# poesp_1_1.net
KiCad netlist of a schematic drawn in EAGLE
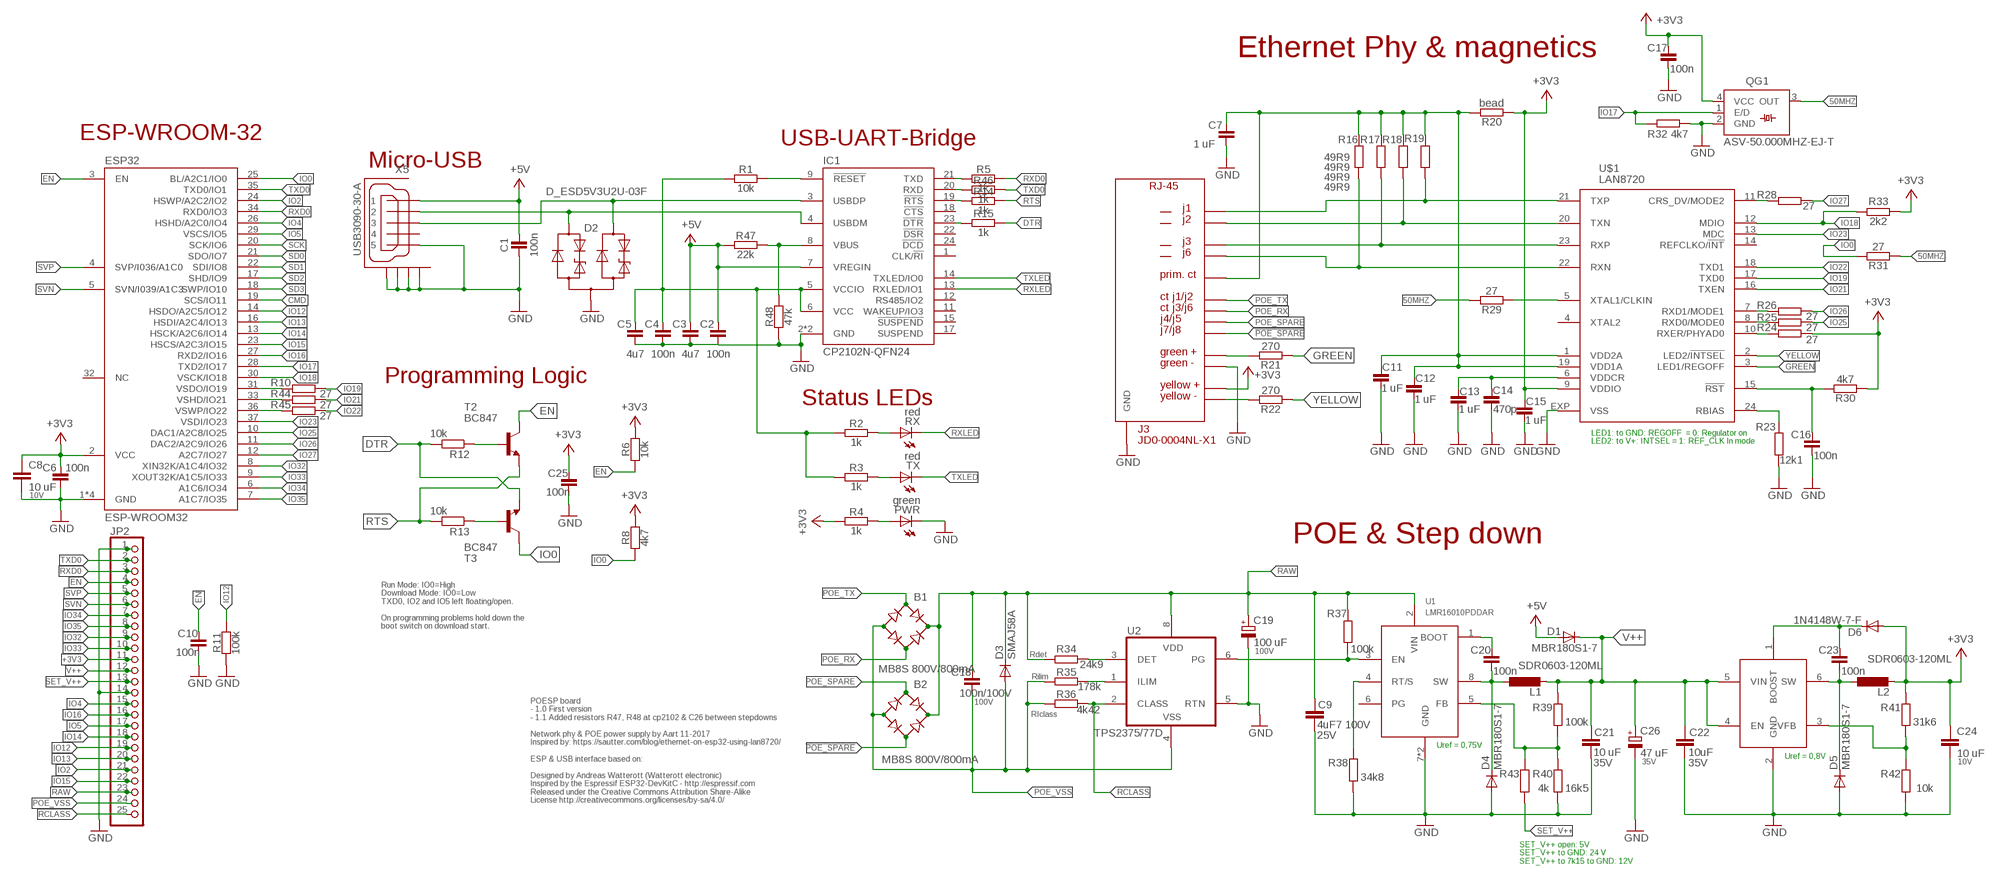
[diagram p0: schematic, sheet 1]

(export (version "E")
  (design (tool "Eeschema 10.0.6"))
  (components
    (comp (ref "B1")
      (value "MB8S 800V/800mA")
      (footprint "eagle-import:MBS")
      (libsource (lib "eagle-import") (part "BS10"))
    )
    (comp (ref "B2")
      (value "MB8S 800V/800mA")
      (footprint "eagle-import:MBS")
      (libsource (lib "eagle-import") (part "BS10"))
    )
    (comp (ref "C1")
      (value "100n")
      (footprint "eagle-import:C0603")
      (libsource (lib "eagle-import") (part "CAPACITOR-0603"))
    )
    (comp (ref "C2")
      (value "100n")
      (footprint "eagle-import:C0603")
      (libsource (lib "eagle-import") (part "CAPACITOR-0603"))
    )
    (comp (ref "C3")
      (value "4u7")
      (footprint "eagle-import:C0805")
      (libsource (lib "eagle-import") (part "CAPACITOR-0805"))
    )
    (comp (ref "C4")
      (value "100n")
      (footprint "eagle-import:C0603")
      (libsource (lib "eagle-import") (part "CAPACITOR-0603"))
    )
    (comp (ref "C5")
      (value "4u7")
      (footprint "eagle-import:C0805")
      (libsource (lib "eagle-import") (part "CAPACITOR-0805"))
    )
    (comp (ref "C6")
      (value "100n")
      (footprint "eagle-import:C0603")
      (libsource (lib "eagle-import") (part "CAPACITOR-0603"))
    )
    (comp (ref "C7")
      (value "1 uF")
      (footprint "eagle-import:C0603")
      (libsource (lib "eagle-import") (part "CAPACITOR-0603"))
    )
    (comp (ref "C8")
      (value "10 uF")
      (footprint "eagle-import:C0805K")
      (fields (field (name "VOLTAGE") "10V"))
      (libsource (lib "eagle-import") (part "C-EUC0805K"))
    )
    (comp (ref "C9")
      (value "4uF7 100V")
      (footprint "eagle-import:C1210K")
      (fields (field (name "VOLTAGE") "25V"))
      (libsource (lib "eagle-import") (part "C-EUC1210K"))
    )
    (comp (ref "C10")
      (value "100n")
      (footprint "eagle-import:C0603")
      (libsource (lib "eagle-import") (part "CAPACITOR-0603"))
    )
    (comp (ref "C11")
      (value "1 uF")
      (footprint "eagle-import:C0603")
      (libsource (lib "eagle-import") (part "CAPACITOR-0603"))
    )
    (comp (ref "C12")
      (value "1 uF")
      (footprint "eagle-import:C0603")
      (libsource (lib "eagle-import") (part "CAPACITOR-0603"))
    )
    (comp (ref "C13")
      (value "1 uF")
      (footprint "eagle-import:C0603")
      (libsource (lib "eagle-import") (part "CAPACITOR-0603"))
    )
    (comp (ref "C14")
      (value "470p")
      (footprint "eagle-import:C0603")
      (libsource (lib "eagle-import") (part "CAPACITOR-0603"))
    )
    (comp (ref "C15")
      (value "1 uF")
      (footprint "eagle-import:C0603")
      (libsource (lib "eagle-import") (part "CAPACITOR-0603"))
    )
    (comp (ref "C16")
      (value "100n")
      (footprint "eagle-import:C0603")
      (libsource (lib "eagle-import") (part "CAPACITOR-0603"))
    )
    (comp (ref "C17")
      (value "100n")
      (footprint "eagle-import:C0603")
      (libsource (lib "eagle-import") (part "CAPACITOR-0603"))
    )
    (comp (ref "C18")
      (value "100n/100V")
      (footprint "eagle-import:C0603")
      (fields (field (name "VOLTAGE") "100V"))
      (libsource (lib "eagle-import") (part "CAPACITOR-0603"))
    )
    (comp (ref "C19")
      (value "100 uF")
      (footprint "eagle-import:E5-10,5")
      (fields (field (name "VOLTAGE") "100V"))
      (libsource (lib "eagle-import") (part "CPOL-EUE5-10.5"))
    )
    (comp (ref "C20")
      (value "100n")
      (footprint "eagle-import:C0603")
      (libsource (lib "eagle-import") (part "CAPACITOR-0603"))
    )
    (comp (ref "C21")
      (value "10 uF")
      (footprint "eagle-import:C1210K")
      (fields (field (name "VOLTAGE") "35V"))
      (libsource (lib "eagle-import") (part "C-EUC1210K"))
    )
    (comp (ref "C22")
      (value "10uF")
      (footprint "eagle-import:C1210K")
      (fields (field (name "VOLTAGE") "35V"))
      (libsource (lib "eagle-import") (part "C-EUC1210K"))
    )
    (comp (ref "C23")
      (value "100n")
      (footprint "eagle-import:C0603")
      (libsource (lib "eagle-import") (part "CAPACITOR-0603"))
    )
    (comp (ref "C24")
      (value "10 uF")
      (footprint "eagle-import:C0805K")
      (fields (field (name "VOLTAGE") "10V"))
      (libsource (lib "eagle-import") (part "C-EUC0805K"))
    )
    (comp (ref "C25")
      (value "100n")
      (footprint "eagle-import:C0603")
      (libsource (lib "eagle-import") (part "CAPACITOR-0603"))
    )
    (comp (ref "C26")
      (value "47 uF")
      (footprint "eagle-import:E2,5-6E")
      (fields (field (name "VOLTAGE") "35V"))
      (libsource (lib "eagle-import") (part "CPOL-EUE2,5-6E"))
    )
    (comp (ref "D1")
      (value "MBR180S1-7")
      (footprint "eagle-import:SOD-123_MINI-SMA")
      (libsource (lib "eagle-import") (part "CGRM400-G1"))
    )
    (comp (ref "D2")
      (value "D_ESD5V3U2U-03F")
      (footprint "eagle-import:SOT723")
      (libsource (lib "eagle-import") (part "D_ESD5V3U2U-03F"))
    )
    (comp (ref "D3")
      (value "SMAJ58A")
      (footprint "eagle-import:DO214AC")
      (libsource (lib "eagle-import") (part "DIODE-DO214AC"))
    )
    (comp (ref "D4")
      (value "MBR180S1-7")
      (footprint "eagle-import:SOD-123_MINI-SMA")
      (libsource (lib "eagle-import") (part "CGRM400-G1"))
    )
    (comp (ref "D5")
      (value "MBR180S1-7")
      (footprint "eagle-import:SOD-123_MINI-SMA")
      (libsource (lib "eagle-import") (part "CGRM400-G1"))
    )
    (comp (ref "D6")
      (value "1N4148W-7-F")
      (footprint "eagle-import:SOD-123_MINI-SMA")
      (libsource (lib "eagle-import") (part "CGRM400-G1"))
    )
    (comp (ref "ESP32")
      (value "ESP-WROOM32")
      (footprint "eagle-import:ESP-WROOM32")
      (libsource (lib "eagle-import") (part "ESP-WROOM32"))
    )
    (comp (ref "IC1")
      (value "CP2102N-QFN24")
      (footprint "eagle-import:QFN24-PAD")
      (libsource (lib "eagle-import") (part "CP2102N-QFN24"))
    )
    (comp (ref "IC3")
      (value "MCP16301/H")
      (footprint "eagle-import:SOT23-6")
      (libsource (lib "eagle-import") (part "MCP16301/H"))
    )
    (comp (ref "J3")
      (value "JD0-0004NL-X1")
      (footprint "eagle-import:JD0")
      (libsource (lib "eagle-import") (part "JD0-0004NL-X1"))
    )
    (comp (ref "JP2")
      (value "PINHD-1X25")
      (footprint "eagle-import:1X25")
      (libsource (lib "eagle-import") (part "PINHD-1X25"))
    )
    (comp (ref "L1")
      (value "SDR0603-120ML")
      (footprint "eagle-import:POWER-CHOKE_WE-TPC")
      (libsource (lib "eagle-import") (part "L-EUWE-TPC"))
    )
    (comp (ref "L2")
      (value "SDR0603-120ML")
      (footprint "eagle-import:POWER-CHOKE_WE-TPC")
      (libsource (lib "eagle-import") (part "L-EUWE-TPC"))
    )
    (comp (ref "PWR")
      (value "green")
      (footprint "eagle-import:C0603")
      (libsource (lib "eagle-import") (part "LED-0603"))
    )
    (comp (ref "QG1")
      (value "ASV-50.000MHZ-EJ-T")
      (footprint "eagle-import:SM77H")
      (libsource (lib "eagle-import") (part "SM77H"))
    )
    (comp (ref "R1")
      (value "10k")
      (footprint "eagle-import:C0603")
      (libsource (lib "eagle-import") (part "RESISTOR-0603"))
    )
    (comp (ref "R2")
      (value "1k")
      (footprint "eagle-import:C0603")
      (libsource (lib "eagle-import") (part "RESISTOR-0603"))
    )
    (comp (ref "R3")
      (value "1k")
      (footprint "eagle-import:C0603")
      (libsource (lib "eagle-import") (part "RESISTOR-0603"))
    )
    (comp (ref "R4")
      (value "1k")
      (footprint "eagle-import:C0603")
      (libsource (lib "eagle-import") (part "RESISTOR-0603"))
    )
    (comp (ref "R5")
      (value "1k")
      (footprint "eagle-import:C0603")
      (libsource (lib "eagle-import") (part "RESISTOR-0603"))
    )
    (comp (ref "R6")
      (value "10k")
      (footprint "eagle-import:C0603")
      (libsource (lib "eagle-import") (part "RESISTOR-0603"))
    )
    (comp (ref "R8")
      (value "4k7")
      (footprint "eagle-import:C0603")
      (libsource (lib "eagle-import") (part "RESISTOR-0603"))
    )
    (comp (ref "R10")
      (value "27")
      (footprint "eagle-import:C0603")
      (libsource (lib "eagle-import") (part "RESISTOR-0603"))
    )
    (comp (ref "R11")
      (value "100k")
      (footprint "eagle-import:C0603")
      (libsource (lib "eagle-import") (part "RESISTOR-0603"))
    )
    (comp (ref "R12")
      (value "10k")
      (footprint "eagle-import:R0603")
      (libsource (lib "eagle-import") (part "R-EU_R0603"))
    )
    (comp (ref "R13")
      (value "10k")
      (footprint "eagle-import:R0603")
      (libsource (lib "eagle-import") (part "R-EU_R0603"))
    )
    (comp (ref "R14")
      (value "1k")
      (footprint "eagle-import:C0603")
      (libsource (lib "eagle-import") (part "RESISTOR-0603"))
    )
    (comp (ref "R15")
      (value "1k")
      (footprint "eagle-import:C0603")
      (libsource (lib "eagle-import") (part "RESISTOR-0603"))
    )
    (comp (ref "R16")
      (value "49R9")
      (footprint "eagle-import:C0603")
      (libsource (lib "eagle-import") (part "RESISTOR-0603"))
    )
    (comp (ref "R17")
      (value "49R9")
      (footprint "eagle-import:C0603")
      (libsource (lib "eagle-import") (part "RESISTOR-0603"))
    )
    (comp (ref "R18")
      (value "49R9")
      (footprint "eagle-import:C0603")
      (libsource (lib "eagle-import") (part "RESISTOR-0603"))
    )
    (comp (ref "R19")
      (value "49R9")
      (footprint "eagle-import:C0603")
      (libsource (lib "eagle-import") (part "RESISTOR-0603"))
    )
    (comp (ref "R20")
      (value "bead")
      (footprint "eagle-import:C0603")
      (libsource (lib "eagle-import") (part "RESISTOR-0603"))
    )
    (comp (ref "R21")
      (value "270")
      (footprint "eagle-import:C0603")
      (libsource (lib "eagle-import") (part "RESISTOR-0603"))
    )
    (comp (ref "R22")
      (value "270")
      (footprint "eagle-import:C0603")
      (libsource (lib "eagle-import") (part "RESISTOR-0603"))
    )
    (comp (ref "R23")
      (value "12k1")
      (footprint "eagle-import:C0603")
      (libsource (lib "eagle-import") (part "RESISTOR-0603"))
    )
    (comp (ref "R24")
      (value "27")
      (footprint "eagle-import:C0603")
      (libsource (lib "eagle-import") (part "RESISTOR-0603"))
    )
    (comp (ref "R25")
      (value "27")
      (footprint "eagle-import:C0603")
      (libsource (lib "eagle-import") (part "RESISTOR-0603"))
    )
    (comp (ref "R26")
      (value "27")
      (footprint "eagle-import:C0603")
      (libsource (lib "eagle-import") (part "RESISTOR-0603"))
    )
    (comp (ref "R28")
      (value "27")
      (footprint "eagle-import:C0603")
      (libsource (lib "eagle-import") (part "RESISTOR-0603"))
    )
    (comp (ref "R29")
      (value "27")
      (footprint "eagle-import:C0603")
      (libsource (lib "eagle-import") (part "RESISTOR-0603"))
    )
    (comp (ref "R30")
      (value "4k7")
      (footprint "eagle-import:C0603")
      (libsource (lib "eagle-import") (part "RESISTOR-0603"))
    )
    (comp (ref "R31")
      (value "27")
      (footprint "eagle-import:C0603")
      (libsource (lib "eagle-import") (part "RESISTOR-0603"))
    )
    (comp (ref "R32")
      (value "4k7")
      (footprint "eagle-import:C0603")
      (libsource (lib "eagle-import") (part "RESISTOR-0603"))
    )
    (comp (ref "R33")
      (value "2k2")
      (footprint "eagle-import:C0603")
      (libsource (lib "eagle-import") (part "RESISTOR-0603"))
    )
    (comp (ref "R34")
      (value "24k9")
      (footprint "eagle-import:C0603")
      (fields (field (name "FUNCTION") "Rdet"))
      (libsource (lib "eagle-import") (part "RESISTOR-0603"))
    )
    (comp (ref "R35")
      (value "178k")
      (footprint "eagle-import:C0603")
      (fields (field (name "FUNCTION") "Rilim"))
      (libsource (lib "eagle-import") (part "RESISTOR-0603"))
    )
    (comp (ref "R36")
      (value "4k42")
      (footprint "eagle-import:C0603")
      (fields (field (name "FUNCTION") "RIclass"))
      (libsource (lib "eagle-import") (part "RESISTOR-0603"))
    )
    (comp (ref "R37")
      (value "100k")
      (footprint "eagle-import:C0603")
      (libsource (lib "eagle-import") (part "RESISTOR-0603"))
    )
    (comp (ref "R38")
      (value "34k8")
      (footprint "eagle-import:C0603")
      (fields (field (name "FUNCTION") "Rdet"))
      (libsource (lib "eagle-import") (part "RESISTOR-0603"))
    )
    (comp (ref "R39")
      (value "100k")
      (footprint "eagle-import:C0603")
      (fields (field (name "FUNCTION") "Rdet"))
      (libsource (lib "eagle-import") (part "RESISTOR-0603"))
    )
    (comp (ref "R40")
      (value "16k5")
      (footprint "eagle-import:C0603")
      (fields (field (name "FUNCTION") "Rdet"))
      (libsource (lib "eagle-import") (part "RESISTOR-0603"))
    )
    (comp (ref "R41")
      (value "31k6")
      (footprint "eagle-import:C0603")
      (fields (field (name "FUNCTION") "Rdet"))
      (libsource (lib "eagle-import") (part "RESISTOR-0603"))
    )
    (comp (ref "R42")
      (value "10k")
      (footprint "eagle-import:C0603")
      (fields (field (name "FUNCTION") "Rdet"))
      (libsource (lib "eagle-import") (part "RESISTOR-0603"))
    )
    (comp (ref "R43")
      (value "4k")
      (footprint "eagle-import:C0603")
      (fields (field (name "FUNCTION") "Rdet"))
      (libsource (lib "eagle-import") (part "RESISTOR-0603"))
    )
    (comp (ref "R44")
      (value "27")
      (footprint "eagle-import:C0603")
      (libsource (lib "eagle-import") (part "RESISTOR-0603"))
    )
    (comp (ref "R45")
      (value "27")
      (footprint "eagle-import:C0603")
      (libsource (lib "eagle-import") (part "RESISTOR-0603"))
    )
    (comp (ref "R46")
      (value "1k")
      (footprint "eagle-import:C0603")
      (libsource (lib "eagle-import") (part "RESISTOR-0603"))
    )
    (comp (ref "R47")
      (value "22k")
      (footprint "eagle-import:C0603")
      (libsource (lib "eagle-import") (part "RESISTOR-0603"))
    )
    (comp (ref "R48")
      (value "47k")
      (footprint "eagle-import:C0603")
      (libsource (lib "eagle-import") (part "RESISTOR-0603"))
    )
    (comp (ref "RX")
      (value "red")
      (footprint "eagle-import:C0603")
      (libsource (lib "eagle-import") (part "LED-0603"))
    )
    (comp (ref "T2")
      (value "BC847")
      (footprint "eagle-import:SOT23")
      (libsource (lib "eagle-import") (part "BC847"))
    )
    (comp (ref "T3")
      (value "BC847")
      (footprint "eagle-import:SOT23")
      (libsource (lib "eagle-import") (part "BC847"))
    )
    (comp (ref "TX")
      (value "red")
      (footprint "eagle-import:C0603")
      (libsource (lib "eagle-import") (part "LED-0603"))
    )
    (comp (ref "U$1")
      (value "LAN8720")
      (footprint "eagle-import:QFN24")
      (libsource (lib "eagle-import") (part "LAN8720"))
    )
    (comp (ref "U1")
      (value "LMR16010PDDAR")
      (footprint "eagle-import:HSOIC8")
      (libsource (lib "eagle-import") (part "LMR16010PDDAR"))
    )
    (comp (ref "U2")
      (value "TPS2375/77D")
      (footprint "eagle-import:SO08")
      (libsource (lib "eagle-import") (part "TPS2375/77D"))
    )
    (comp (ref "X5")
      (value "USB3090-30-A")
      (footprint "eagle-import:USB3090-30-A")
      (libsource (lib "eagle-import") (part "USB3090-30-A"))
    )
  )
  (nets
    (net (code "1") (name "+3V3") (class "Default")
      (node (ref "C15") (pin "2") (pinfunction "2_2") (pintype "passive"))
      (node (ref "C17") (pin "2") (pinfunction "2_2") (pintype "passive"))
      (node (ref "C24") (pin "1") (pinfunction "1_1") (pintype "passive"))
      (node (ref "C25") (pin "2") (pinfunction "2_2") (pintype "passive"))
      (node (ref "C6") (pin "2") (pinfunction "2_2") (pintype "passive"))
      (node (ref "C8") (pin "1") (pinfunction "1_1") (pintype "passive"))
      (node (ref "D6") (pin "A") (pinfunction "A_A") (pintype "passive"))
      (node (ref "ESP32") (pin "2") (pinfunction "VCC_2") (pintype "power_in"))
      (node (ref "J3") (pin "P$14") (pinfunction "P$14_P$14") (pintype "bidirectional"))
      (node (ref "JP2") (pin "11") (pinfunction "11_11") (pintype "passive"))
      (node (ref "L2") (pin "2") (pinfunction "2_2") (pintype "passive"))
      (node (ref "QG1") (pin "4") (pinfunction "VCC_4") (pintype "power_in"))
      (node (ref "R20") (pin "1") (pinfunction "1_1") (pintype "passive"))
      (node (ref "R24") (pin "1") (pinfunction "1_1") (pintype "passive"))
      (node (ref "R30") (pin "1") (pinfunction "1_1") (pintype "passive"))
      (node (ref "R33") (pin "1") (pinfunction "1_1") (pintype "passive"))
      (node (ref "R4") (pin "1") (pinfunction "1_1") (pintype "passive"))
      (node (ref "R41") (pin "1") (pinfunction "1_1") (pintype "passive"))
      (node (ref "R6") (pin "2") (pinfunction "2_2") (pintype "passive"))
      (node (ref "R8") (pin "2") (pinfunction "2_2") (pintype "passive"))
      (node (ref "U$1") (pin "9") (pinfunction "VDDIO_9") (pintype "power_in"))
    )
    (net (code "2") (name "+5V") (class "Default")
      (node (ref "C1") (pin "2") (pinfunction "2_2") (pintype "passive"))
      (node (ref "C2") (pin "2") (pinfunction "2_2") (pintype "passive"))
      (node (ref "C3") (pin "2") (pinfunction "2_2") (pintype "passive"))
      (node (ref "D1") (pin "A") (pinfunction "A_A") (pintype "passive"))
      (node (ref "IC1") (pin "7") (pinfunction "VREGIN_7") (pintype "power_in"))
      (node (ref "R47") (pin "1") (pinfunction "1_1") (pintype "passive"))
      (node (ref "X5") (pin "1") (pinfunction "1_1") (pintype "input"))
    )
    (net (code "3") (name "/~{POE_SPARE}") (class "Default")
      (node (ref "B2") (pin "AC2") (pinfunction "AC2_AC2") (pintype "passive"))
      (node (ref "J3") (pin "P$8") (pinfunction "P$8_P$8") (pintype "bidirectional"))
    )
    (net (code "4") (name "50MHZ") (class "Default")
      (node (ref "QG1") (pin "3") (pinfunction "OUT_3") (pintype "output"))
      (node (ref "R29") (pin "2") (pinfunction "2_2") (pintype "passive"))
      (node (ref "R31") (pin "1") (pinfunction "1_1") (pintype "passive"))
    )
    (net (code "5") (name "CMD") (class "Default")
      (node (ref "ESP32") (pin "19") (pinfunction "SCS/IO11_19") (pintype "bidirectional"))
    )
    (net (code "6") (name "DTR") (class "Default")
      (node (ref "R12") (pin "2") (pinfunction "2_2") (pintype "passive"))
      (node (ref "R15") (pin "2") (pinfunction "2_2") (pintype "passive"))
      (node (ref "T3") (pin "2") (pinfunction "E_2") (pintype "passive"))
    )
    (net (code "7") (name "EN") (class "Default")
      (node (ref "C10") (pin "2") (pinfunction "2_2") (pintype "passive"))
      (node (ref "ESP32") (pin "3") (pinfunction "EN_3") (pintype "bidirectional"))
      (node (ref "JP2") (pin "4") (pinfunction "4_4") (pintype "passive"))
      (node (ref "R6") (pin "1") (pinfunction "1_1") (pintype "passive"))
      (node (ref "T2") (pin "3") (pinfunction "C_3") (pintype "passive"))
    )
    (net (code "8") (name "GND") (class "Default")
      (node (ref "C1") (pin "1") (pinfunction "1_1") (pintype "passive"))
      (node (ref "C10") (pin "1") (pinfunction "1_1") (pintype "passive"))
      (node (ref "C11") (pin "1") (pinfunction "1_1") (pintype "passive"))
      (node (ref "C12") (pin "1") (pinfunction "1_1") (pintype "passive"))
      (node (ref "C13") (pin "1") (pinfunction "1_1") (pintype "passive"))
      (node (ref "C14") (pin "1") (pinfunction "1_1") (pintype "passive"))
      (node (ref "C15") (pin "1") (pinfunction "1_1") (pintype "passive"))
      (node (ref "C16") (pin "1") (pinfunction "1_1") (pintype "passive"))
      (node (ref "C17") (pin "1") (pinfunction "1_1") (pintype "passive"))
      (node (ref "C19") (pin "-") (pinfunction "-_-") (pintype "passive"))
      (node (ref "C2") (pin "1") (pinfunction "1_1") (pintype "passive"))
      (node (ref "C21") (pin "2") (pinfunction "2_2") (pintype "passive"))
      (node (ref "C22") (pin "2") (pinfunction "2_2") (pintype "passive"))
      (node (ref "C24") (pin "2") (pinfunction "2_2") (pintype "passive"))
      (node (ref "C25") (pin "1") (pinfunction "1_1") (pintype "passive"))
      (node (ref "C26") (pin "-") (pinfunction "-_-") (pintype "passive"))
      (node (ref "C3") (pin "1") (pinfunction "1_1") (pintype "passive"))
      (node (ref "C4") (pin "1") (pinfunction "1_1") (pintype "passive"))
      (node (ref "C5") (pin "1") (pinfunction "1_1") (pintype "passive"))
      (node (ref "C6") (pin "1") (pinfunction "1_1") (pintype "passive"))
      (node (ref "C7") (pin "1") (pinfunction "1_1") (pintype "passive"))
      (node (ref "C8") (pin "2") (pinfunction "2_2") (pintype "passive"))
      (node (ref "C9") (pin "2") (pinfunction "2_2") (pintype "passive"))
      (node (ref "D2") (pin "3") (pinfunction "A_3") (pintype "passive"))
      (node (ref "D4") (pin "A") (pinfunction "A_A") (pintype "passive"))
      (node (ref "D5") (pin "A") (pinfunction "A_A") (pintype "passive"))
      (node (ref "ESP32") (pin "1") (pinfunction "GND_1") (pintype "power_in"))
      (node (ref "ESP32") (pin "15") (pinfunction "GND_15") (pintype "power_in"))
      (node (ref "ESP32") (pin "38") (pinfunction "GND_38") (pintype "power_in"))
      (node (ref "ESP32") (pin "TP") (pinfunction "GND_TP") (pintype "power_in"))
      (node (ref "IC1") (pin "2") (pinfunction "GND_2") (pintype "power_in"))
      (node (ref "IC1") (pin "TP") (pinfunction "GND_TP") (pintype "power_in"))
      (node (ref "IC3") (pin "2") (pinfunction "GND_2") (pintype "power_in"))
      (node (ref "J3") (pin "P$11") (pinfunction "P$11_P$11") (pintype "bidirectional"))
      (node (ref "J3") (pin "P$21") (pinfunction "GND_P$21") (pintype "bidirectional"))
      (node (ref "J3") (pin "P$22") (pinfunction "GND_P$22") (pintype "bidirectional"))
      (node (ref "J3") (pin "P$23") (pinfunction "GND_P$23") (pintype "bidirectional"))
      (node (ref "J3") (pin "P$24") (pinfunction "GND_P$24") (pintype "bidirectional"))
      (node (ref "JP2") (pin "1") (pinfunction "1_1") (pintype "passive"))
      (node (ref "JP2") (pin "14") (pinfunction "14_14") (pintype "passive"))
      (node (ref "PWR") (pin "C") (pinfunction "C_C") (pintype "passive"))
      (node (ref "QG1") (pin "2") (pinfunction "GND_2") (pintype "power_in"))
      (node (ref "R11") (pin "1") (pinfunction "1_1") (pintype "passive"))
      (node (ref "R23") (pin "1") (pinfunction "1_1") (pintype "passive"))
      (node (ref "R32") (pin "1") (pinfunction "1_1") (pintype "passive"))
      (node (ref "R38") (pin "2") (pinfunction "2_2") (pintype "passive"))
      (node (ref "R40") (pin "2") (pinfunction "2_2") (pintype "passive"))
      (node (ref "R42") (pin "2") (pinfunction "2_2") (pintype "passive"))
      (node (ref "R48") (pin "1") (pinfunction "1_1") (pintype "passive"))
      (node (ref "U$1") (pin "EXP") (pinfunction "VSS_EXP") (pintype "power_in"))
      (node (ref "U1") (pin "7") (pinfunction "GND_7") (pintype "bidirectional"))
      (node (ref "U1") (pin "P$9") (pinfunction "GND_P$9") (pintype "bidirectional"))
      (node (ref "U2") (pin "5") (pinfunction "RTN_5") (pintype "output"))
      (node (ref "X5") (pin "5") (pinfunction "5_5") (pintype "input"))
      (node (ref "X5") (pin "GND2") (pinfunction "GND1_GND2") (pintype "bidirectional"))
      (node (ref "X5") (pin "GND3") (pinfunction "GND2_GND3") (pintype "bidirectional"))
      (node (ref "X5") (pin "P$1") (pinfunction "GND3_P$1") (pintype "bidirectional"))
      (node (ref "X5") (pin "P$2") (pinfunction "GND4_P$2") (pintype "bidirectional"))
    )
    (net (code "9") (name "GREEN") (class "Default")
      (node (ref "R21") (pin "1") (pinfunction "1_1") (pintype "passive"))
      (node (ref "U$1") (pin "3") (pinfunction "LED1/REGOFF_3") (pintype "bidirectional"))
    )
    (net (code "10") (name "IO0") (class "Default")
      (node (ref "ESP32") (pin "25") (pinfunction "BL/A2C1/IO0_25") (pintype "bidirectional"))
      (node (ref "R31") (pin "2") (pinfunction "2_2") (pintype "passive"))
      (node (ref "R8") (pin "1") (pinfunction "1_1") (pintype "passive"))
      (node (ref "T3") (pin "3") (pinfunction "C_3") (pintype "passive"))
    )
    (net (code "11") (name "IO2") (class "Default")
      (node (ref "ESP32") (pin "24") (pinfunction "HSWP/A2C2/IO2_24") (pintype "bidirectional"))
      (node (ref "JP2") (pin "21") (pinfunction "21_21") (pintype "passive"))
    )
    (net (code "12") (name "IO4") (class "Default")
      (node (ref "ESP32") (pin "26") (pinfunction "HSHD/A2C0/IO4_26") (pintype "bidirectional"))
      (node (ref "JP2") (pin "15") (pinfunction "15_15") (pintype "passive"))
    )
    (net (code "13") (name "IO5") (class "Default")
      (node (ref "ESP32") (pin "29") (pinfunction "VSCS/IO5_29") (pintype "bidirectional"))
      (node (ref "JP2") (pin "17") (pinfunction "17_17") (pintype "passive"))
    )
    (net (code "14") (name "IO12") (class "Default")
      (node (ref "ESP32") (pin "14") (pinfunction "HSDO/A2C5/IO12_14") (pintype "bidirectional"))
      (node (ref "JP2") (pin "19") (pinfunction "19_19") (pintype "passive"))
      (node (ref "R11") (pin "2") (pinfunction "2_2") (pintype "passive"))
    )
    (net (code "15") (name "IO13") (class "Default")
      (node (ref "ESP32") (pin "16") (pinfunction "HSDI/A2C4/IO13_16") (pintype "bidirectional"))
      (node (ref "JP2") (pin "20") (pinfunction "20_20") (pintype "passive"))
    )
    (net (code "16") (name "IO14") (class "Default")
      (node (ref "ESP32") (pin "13") (pinfunction "HSCK/A2C6/IO14_13") (pintype "bidirectional"))
      (node (ref "JP2") (pin "18") (pinfunction "18_18") (pintype "passive"))
    )
    (net (code "17") (name "IO15") (class "Default")
      (node (ref "ESP32") (pin "23") (pinfunction "HSCS/A2C3/IO15_23") (pintype "bidirectional"))
      (node (ref "JP2") (pin "22") (pinfunction "22_22") (pintype "passive"))
    )
    (net (code "18") (name "IO16") (class "Default")
      (node (ref "ESP32") (pin "27") (pinfunction "RXD2/IO16_27") (pintype "bidirectional"))
      (node (ref "JP2") (pin "16") (pinfunction "16_16") (pintype "passive"))
    )
    (net (code "19") (name "IO17") (class "Default")
      (node (ref "ESP32") (pin "28") (pinfunction "TXD2/IO17_28") (pintype "bidirectional"))
      (node (ref "QG1") (pin "1") (pinfunction "E/D_1") (pintype "input"))
      (node (ref "R32") (pin "2") (pinfunction "2_2") (pintype "passive"))
    )
    (net (code "20") (name "IO18") (class "Default")
      (node (ref "ESP32") (pin "30") (pinfunction "VSCK/IO18_30") (pintype "bidirectional"))
      (node (ref "R33") (pin "2") (pinfunction "2_2") (pintype "passive"))
      (node (ref "U$1") (pin "12") (pinfunction "MDIO_12") (pintype "bidirectional"))
    )
    (net (code "21") (name "IO19") (class "Default")
      (node (ref "R10") (pin "1") (pinfunction "1_1") (pintype "passive"))
      (node (ref "U$1") (pin "17") (pinfunction "TXD0_17") (pintype "bidirectional"))
    )
    (net (code "22") (name "IO21") (class "Default")
      (node (ref "R44") (pin "1") (pinfunction "1_1") (pintype "passive"))
      (node (ref "U$1") (pin "16") (pinfunction "TXEN_16") (pintype "bidirectional"))
    )
    (net (code "23") (name "IO22") (class "Default")
      (node (ref "R45") (pin "1") (pinfunction "1_1") (pintype "passive"))
      (node (ref "U$1") (pin "18") (pinfunction "TXD1_18") (pintype "bidirectional"))
    )
    (net (code "24") (name "IO23") (class "Default")
      (node (ref "ESP32") (pin "37") (pinfunction "VSDI/IO23_37") (pintype "bidirectional"))
      (node (ref "U$1") (pin "13") (pinfunction "MDC_13") (pintype "bidirectional"))
    )
    (net (code "25") (name "IO25") (class "Default")
      (node (ref "ESP32") (pin "10") (pinfunction "DAC1/A2C8/IO25_10") (pintype "bidirectional"))
      (node (ref "R25") (pin "1") (pinfunction "1_1") (pintype "passive"))
    )
    (net (code "26") (name "IO26") (class "Default")
      (node (ref "ESP32") (pin "11") (pinfunction "DAC2/A2C9/IO26_11") (pintype "bidirectional"))
      (node (ref "R26") (pin "1") (pinfunction "1_1") (pintype "passive"))
    )
    (net (code "27") (name "IO27") (class "Default")
      (node (ref "ESP32") (pin "12") (pinfunction "A2C7/IO27_12") (pintype "bidirectional"))
      (node (ref "R28") (pin "1") (pinfunction "1_1") (pintype "passive"))
    )
    (net (code "28") (name "IO32") (class "Default")
      (node (ref "ESP32") (pin "8") (pinfunction "XIN32K/A1C4/IO32_8") (pintype "bidirectional"))
      (node (ref "JP2") (pin "9") (pinfunction "9_9") (pintype "passive"))
    )
    (net (code "29") (name "IO33") (class "Default")
      (node (ref "ESP32") (pin "9") (pinfunction "XOUT32K/A1C5/IO33_9") (pintype "bidirectional"))
      (node (ref "JP2") (pin "10") (pinfunction "10_10") (pintype "passive"))
    )
    (net (code "30") (name "IO34") (class "Default")
      (node (ref "ESP32") (pin "6") (pinfunction "A1C6/IO34_6") (pintype "bidirectional"))
      (node (ref "JP2") (pin "7") (pinfunction "7_7") (pintype "passive"))
    )
    (net (code "31") (name "IO35") (class "Default")
      (node (ref "ESP32") (pin "7") (pinfunction "A1C7/IO35_7") (pintype "bidirectional"))
      (node (ref "JP2") (pin "8") (pinfunction "8_8") (pintype "passive"))
    )
    (net (code "32") (name "Net-(D2-C1)") (class "Default")
      (node (ref "D2") (pin "1") (pinfunction "C1_1") (pintype "passive"))
      (node (ref "IC1") (pin "4") (pinfunction "USBDM_4") (pintype "bidirectional"))
      (node (ref "X5") (pin "2") (pinfunction "2_2") (pintype "input"))
    )
    (net (code "33") (name "Net-(D2-C2)") (class "Default")
      (node (ref "D2") (pin "2") (pinfunction "C2_2") (pintype "passive"))
      (node (ref "IC1") (pin "3") (pinfunction "USBDP_3") (pintype "bidirectional"))
      (node (ref "X5") (pin "3") (pinfunction "3_3") (pintype "input"))
    )
    (net (code "34") (name "Net-(ESP32-VSDO{slash}IO19)") (class "Default")
      (node (ref "ESP32") (pin "31") (pinfunction "VSDO/IO19_31") (pintype "bidirectional"))
      (node (ref "R10") (pin "2") (pinfunction "2_2") (pintype "passive"))
    )
    (net (code "35") (name "Net-(ESP32-VSHD{slash}IO21)") (class "Default")
      (node (ref "ESP32") (pin "33") (pinfunction "VSHD/IO21_33") (pintype "bidirectional"))
      (node (ref "R44") (pin "2") (pinfunction "2_2") (pintype "passive"))
    )
    (net (code "36") (name "Net-(ESP32-VSWP{slash}IO22)") (class "Default")
      (node (ref "ESP32") (pin "36") (pinfunction "VSWP/IO22_36") (pintype "bidirectional"))
      (node (ref "R45") (pin "2") (pinfunction "2_2") (pintype "passive"))
    )
    (net (code "37") (name "Net-(IC1-RXD)") (class "Default")
      (node (ref "IC1") (pin "20") (pinfunction "RXD_20") (pintype "bidirectional"))
      (node (ref "R46") (pin "1") (pinfunction "1_1") (pintype "passive"))
    )
    (net (code "38") (name "Net-(IC1-TXD)") (class "Default")
      (node (ref "IC1") (pin "21") (pinfunction "TXD_21") (pintype "bidirectional"))
      (node (ref "R5") (pin "1") (pinfunction "1_1") (pintype "passive"))
    )
    (net (code "39") (name "Net-(IC1-VBUS)") (class "Default")
      (node (ref "IC1") (pin "8") (pinfunction "VBUS_8") (pintype "power_in"))
      (node (ref "R47") (pin "2") (pinfunction "2_2") (pintype "passive"))
      (node (ref "R48") (pin "2") (pinfunction "2_2") (pintype "passive"))
    )
    (net (code "40") (name "Net-(IC1-VCC)") (class "Default")
      (node (ref "C4") (pin "2") (pinfunction "2_2") (pintype "passive"))
      (node (ref "C5") (pin "2") (pinfunction "2_2") (pintype "passive"))
      (node (ref "IC1") (pin "5") (pinfunction "VCCIO_5") (pintype "power_in"))
      (node (ref "IC1") (pin "6") (pinfunction "VCC_6") (pintype "power_in"))
      (node (ref "R1") (pin "1") (pinfunction "1_1") (pintype "passive"))
      (node (ref "R2") (pin "1") (pinfunction "1_1") (pintype "passive"))
      (node (ref "R3") (pin "1") (pinfunction "1_1") (pintype "passive"))
    )
    (net (code "41") (name "Net-(IC1-~{DTR})") (class "Default")
      (node (ref "IC1") (pin "23") (pinfunction "~{DTR}_23") (pintype "bidirectional"))
      (node (ref "R15") (pin "1") (pinfunction "1_1") (pintype "passive"))
    )
    (net (code "42") (name "Net-(IC1-~{RESET})") (class "Default")
      (node (ref "IC1") (pin "9") (pinfunction "~{RESET}_9") (pintype "bidirectional"))
      (node (ref "R1") (pin "2") (pinfunction "2_2") (pintype "passive"))
    )
    (net (code "43") (name "Net-(IC1-~{RTS})") (class "Default")
      (node (ref "IC1") (pin "19") (pinfunction "~{RTS}_19") (pintype "bidirectional"))
      (node (ref "R14") (pin "1") (pinfunction "1_1") (pintype "passive"))
    )
    (net (code "44") (name "Net-(IC3-BOOST)") (class "Default")
      (node (ref "C23") (pin "2") (pinfunction "2_2") (pintype "passive"))
      (node (ref "D6") (pin "C") (pinfunction "C_C") (pintype "passive"))
      (node (ref "IC3") (pin "1") (pinfunction "BOOST_1") (pintype "bidirectional"))
    )
    (net (code "45") (name "Net-(IC3-SW)") (class "Default")
      (node (ref "C23") (pin "1") (pinfunction "1_1") (pintype "passive"))
      (node (ref "D5") (pin "C") (pinfunction "C_C") (pintype "passive"))
      (node (ref "IC3") (pin "6") (pinfunction "SW_6") (pintype "power_in"))
      (node (ref "L2") (pin "1") (pinfunction "1_1") (pintype "passive"))
    )
    (net (code "46") (name "Net-(IC3-VFB)") (class "Default")
      (node (ref "IC3") (pin "3") (pinfunction "VFB_3") (pintype "bidirectional"))
      (node (ref "R41") (pin "2") (pinfunction "2_2") (pintype "passive"))
      (node (ref "R42") (pin "1") (pinfunction "1_1") (pintype "passive"))
    )
    (net (code "47") (name "Net-(J3-PadP$12)") (class "Default")
      (node (ref "J3") (pin "P$12") (pinfunction "P$12_P$12") (pintype "bidirectional"))
      (node (ref "R21") (pin "2") (pinfunction "2_2") (pintype "passive"))
    )
    (net (code "48") (name "Net-(J3-PadP$13)") (class "Default")
      (node (ref "J3") (pin "P$13") (pinfunction "P$13_P$13") (pintype "bidirectional"))
      (node (ref "R22") (pin "2") (pinfunction "2_2") (pintype "passive"))
    )
    (net (code "49") (name "Net-(PWR-PadA)") (class "Default")
      (node (ref "PWR") (pin "A") (pinfunction "A_A") (pintype "passive"))
      (node (ref "R4") (pin "2") (pinfunction "2_2") (pintype "passive"))
    )
    (net (code "50") (name "Net-(R2-Pad2)") (class "Default")
      (node (ref "R2") (pin "2") (pinfunction "2_2") (pintype "passive"))
      (node (ref "RX") (pin "A") (pinfunction "A_A") (pintype "passive"))
    )
    (net (code "51") (name "Net-(R3-Pad2)") (class "Default")
      (node (ref "R3") (pin "2") (pinfunction "2_2") (pintype "passive"))
      (node (ref "TX") (pin "A") (pinfunction "A_A") (pintype "passive"))
    )
    (net (code "52") (name "Net-(T2-B)") (class "Default")
      (node (ref "R12") (pin "1") (pinfunction "1_1") (pintype "passive"))
      (node (ref "T2") (pin "1") (pinfunction "B_1") (pintype "passive"))
    )
    (net (code "53") (name "Net-(T3-B)") (class "Default")
      (node (ref "R13") (pin "1") (pinfunction "1_1") (pintype "passive"))
      (node (ref "T3") (pin "1") (pinfunction "B_1") (pintype "passive"))
    )
    (net (code "54") (name "Net-(U$1-CRS_DV{slash}MODE2)") (class "Default")
      (node (ref "R28") (pin "2") (pinfunction "2_2") (pintype "passive"))
      (node (ref "U$1") (pin "11") (pinfunction "CRS_DV/MODE2_11") (pintype "bidirectional"))
    )
    (net (code "55") (name "Net-(U$1-RBIAS)") (class "Default")
      (node (ref "R23") (pin "2") (pinfunction "2_2") (pintype "passive"))
      (node (ref "U$1") (pin "24") (pinfunction "RBIAS_24") (pintype "bidirectional"))
    )
    (net (code "56") (name "Net-(U$1-RXD0{slash}MODE0)") (class "Default")
      (node (ref "R25") (pin "2") (pinfunction "2_2") (pintype "passive"))
      (node (ref "U$1") (pin "8") (pinfunction "RXD0/MODE0_8") (pintype "bidirectional"))
    )
    (net (code "57") (name "Net-(U$1-RXD1{slash}MODE1)") (class "Default")
      (node (ref "R26") (pin "2") (pinfunction "2_2") (pintype "passive"))
      (node (ref "U$1") (pin "7") (pinfunction "RXD1/MODE1_7") (pintype "bidirectional"))
    )
    (net (code "58") (name "Net-(U$1-RXER{slash}PHYAD0)") (class "Default")
      (node (ref "R24") (pin "2") (pinfunction "2_2") (pintype "passive"))
      (node (ref "U$1") (pin "10") (pinfunction "RXER/PHYAD0_10") (pintype "bidirectional"))
    )
    (net (code "59") (name "Net-(U$1-RXN)") (class "Default")
      (node (ref "J3") (pin "P$5") (pinfunction "P$5_P$5") (pintype "bidirectional"))
      (node (ref "R16") (pin "1") (pinfunction "1_1") (pintype "passive"))
      (node (ref "U$1") (pin "22") (pinfunction "RXN_22") (pintype "bidirectional"))
    )
    (net (code "60") (name "Net-(U$1-RXP)") (class "Default")
      (node (ref "J3") (pin "P$3") (pinfunction "P$3_P$3") (pintype "bidirectional"))
      (node (ref "R17") (pin "1") (pinfunction "1_1") (pintype "passive"))
      (node (ref "U$1") (pin "23") (pinfunction "RXP_23") (pintype "bidirectional"))
    )
    (net (code "61") (name "Net-(U$1-TXN)") (class "Default")
      (node (ref "J3") (pin "P$2") (pinfunction "P$2_P$2") (pintype "bidirectional"))
      (node (ref "R18") (pin "1") (pinfunction "1_1") (pintype "passive"))
      (node (ref "U$1") (pin "20") (pinfunction "TXN_20") (pintype "bidirectional"))
    )
    (net (code "62") (name "Net-(U$1-TXP)") (class "Default")
      (node (ref "J3") (pin "P$1") (pinfunction "P$1_P$1") (pintype "bidirectional"))
      (node (ref "R19") (pin "1") (pinfunction "1_1") (pintype "passive"))
      (node (ref "U$1") (pin "21") (pinfunction "TXP_21") (pintype "bidirectional"))
    )
    (net (code "63") (name "Net-(U$1-VDD1A)") (class "Default")
      (node (ref "C11") (pin "2") (pinfunction "2_2") (pintype "passive"))
      (node (ref "C12") (pin "2") (pinfunction "2_2") (pintype "passive"))
      (node (ref "C7") (pin "2") (pinfunction "2_2") (pintype "passive"))
      (node (ref "J3") (pin "P$4") (pinfunction "P$4_P$4") (pintype "bidirectional"))
      (node (ref "R16") (pin "2") (pinfunction "2_2") (pintype "passive"))
      (node (ref "R17") (pin "2") (pinfunction "2_2") (pintype "passive"))
      (node (ref "R18") (pin "2") (pinfunction "2_2") (pintype "passive"))
      (node (ref "R19") (pin "2") (pinfunction "2_2") (pintype "passive"))
      (node (ref "R20") (pin "2") (pinfunction "2_2") (pintype "passive"))
      (node (ref "U$1") (pin "1") (pinfunction "VDD2A_1") (pintype "power_in"))
      (node (ref "U$1") (pin "19") (pinfunction "VDD1A_19") (pintype "power_in"))
    )
    (net (code "64") (name "Net-(U$1-VDDCR)") (class "Default")
      (node (ref "C13") (pin "2") (pinfunction "2_2") (pintype "passive"))
      (node (ref "C14") (pin "2") (pinfunction "2_2") (pintype "passive"))
      (node (ref "U$1") (pin "6") (pinfunction "VDDCR_6") (pintype "power_in"))
    )
    (net (code "65") (name "Net-(U$1-XTAL1{slash}CLKIN)") (class "Default")
      (node (ref "R29") (pin "1") (pinfunction "1_1") (pintype "passive"))
      (node (ref "U$1") (pin "5") (pinfunction "XTAL1/CLKIN_5") (pintype "bidirectional"))
    )
    (net (code "66") (name "Net-(U$1-~{RST})") (class "Default")
      (node (ref "C16") (pin "2") (pinfunction "2_2") (pintype "passive"))
      (node (ref "R30") (pin "2") (pinfunction "2_2") (pintype "passive"))
      (node (ref "U$1") (pin "15") (pinfunction "~{RST}_15") (pintype "bidirectional"))
    )
    (net (code "67") (name "Net-(U1-BOOT)") (class "Default")
      (node (ref "C20") (pin "2") (pinfunction "2_2") (pintype "passive"))
      (node (ref "U1") (pin "1") (pinfunction "BOOT_1") (pintype "bidirectional"))
    )
    (net (code "68") (name "Net-(U1-EN)") (class "Default")
      (node (ref "R37") (pin "2") (pinfunction "2_2") (pintype "passive"))
      (node (ref "U1") (pin "3") (pinfunction "EN_3") (pintype "bidirectional"))
      (node (ref "U2") (pin "6") (pinfunction "PG_6") (pintype "output"))
    )
    (net (code "69") (name "Net-(U1-FB)") (class "Default")
      (node (ref "R39") (pin "2") (pinfunction "2_2") (pintype "passive"))
      (node (ref "R40") (pin "1") (pinfunction "1_1") (pintype "passive"))
      (node (ref "R43") (pin "1") (pinfunction "1_1") (pintype "passive"))
      (node (ref "U1") (pin "5") (pinfunction "FB_5") (pintype "bidirectional"))
    )
    (net (code "70") (name "Net-(U1-RT{slash}S)") (class "Default")
      (node (ref "R38") (pin "1") (pinfunction "1_1") (pintype "passive"))
      (node (ref "U1") (pin "4") (pinfunction "RT/S_4") (pintype "bidirectional"))
    )
    (net (code "71") (name "Net-(U1-SW)") (class "Default")
      (node (ref "C20") (pin "1") (pinfunction "1_1") (pintype "passive"))
      (node (ref "D4") (pin "C") (pinfunction "C_C") (pintype "passive"))
      (node (ref "L1") (pin "1") (pinfunction "1_1") (pintype "passive"))
      (node (ref "U1") (pin "8") (pinfunction "SW_8") (pintype "bidirectional"))
    )
    (net (code "72") (name "Net-(U2-DET)") (class "Default")
      (node (ref "R34") (pin "1") (pinfunction "1_1") (pintype "passive"))
      (node (ref "U2") (pin "3") (pinfunction "DET_3") (pintype "output"))
    )
    (net (code "73") (name "Net-(U2-ILIM)") (class "Default")
      (node (ref "R35") (pin "1") (pinfunction "1_1") (pintype "passive"))
      (node (ref "U2") (pin "1") (pinfunction "ILIM_1") (pintype "output"))
    )
    (net (code "74") (name "POE_RX") (class "Default")
      (node (ref "B1") (pin "AC2") (pinfunction "AC2_AC2") (pintype "passive"))
      (node (ref "J3") (pin "P$10") (pinfunction "P$10_P$10") (pintype "bidirectional"))
    )
    (net (code "75") (name "POE_SPARE") (class "Default")
      (node (ref "B2") (pin "AC1") (pinfunction "AC1_AC1") (pintype "passive"))
      (node (ref "J3") (pin "P$7") (pinfunction "P$7_P$7") (pintype "bidirectional"))
    )
    (net (code "76") (name "POE_TX") (class "Default")
      (node (ref "B1") (pin "AC1") (pinfunction "AC1_AC1") (pintype "passive"))
      (node (ref "J3") (pin "P$9") (pinfunction "P$9_P$9") (pintype "bidirectional"))
    )
    (net (code "77") (name "POE_VSS") (class "Default")
      (node (ref "B1") (pin "-") (pinfunction "-_-") (pintype "passive"))
      (node (ref "B2") (pin "-") (pinfunction "-_-") (pintype "passive"))
      (node (ref "C18") (pin "1") (pinfunction "1_1") (pintype "passive"))
      (node (ref "D3") (pin "A") (pinfunction "A_A") (pintype "passive"))
      (node (ref "JP2") (pin "24") (pinfunction "24_24") (pintype "passive"))
      (node (ref "R35") (pin "2") (pinfunction "2_2") (pintype "passive"))
      (node (ref "R36") (pin "2") (pinfunction "2_2") (pintype "passive"))
      (node (ref "U2") (pin "4") (pinfunction "VSS_4") (pintype "power_in"))
    )
    (net (code "78") (name "RAW") (class "Default")
      (node (ref "B1") (pin "+") (pinfunction "+_+") (pintype "passive"))
      (node (ref "B2") (pin "+") (pinfunction "+_+") (pintype "passive"))
      (node (ref "C18") (pin "2") (pinfunction "2_2") (pintype "passive"))
      (node (ref "C19") (pin "+") (pinfunction "+_+") (pintype "passive"))
      (node (ref "C9") (pin "1") (pinfunction "1_1") (pintype "passive"))
      (node (ref "D3") (pin "C") (pinfunction "C_C") (pintype "passive"))
      (node (ref "JP2") (pin "23") (pinfunction "23_23") (pintype "passive"))
      (node (ref "R34") (pin "2") (pinfunction "2_2") (pintype "passive"))
      (node (ref "R37") (pin "1") (pinfunction "1_1") (pintype "passive"))
      (node (ref "U1") (pin "2") (pinfunction "VIN_2") (pintype "bidirectional"))
      (node (ref "U2") (pin "8") (pinfunction "VDD_8") (pintype "power_in"))
    )
    (net (code "79") (name "RCLASS") (class "Default")
      (node (ref "JP2") (pin "25") (pinfunction "25_25") (pintype "passive"))
      (node (ref "R36") (pin "1") (pinfunction "1_1") (pintype "passive"))
      (node (ref "U2") (pin "2") (pinfunction "CLASS_2") (pintype "output"))
    )
    (net (code "80") (name "RTS") (class "Default")
      (node (ref "R13") (pin "2") (pinfunction "2_2") (pintype "passive"))
      (node (ref "R14") (pin "2") (pinfunction "2_2") (pintype "passive"))
      (node (ref "T2") (pin "2") (pinfunction "E_2") (pintype "passive"))
    )
    (net (code "81") (name "RXD0") (class "Default")
      (node (ref "ESP32") (pin "34") (pinfunction "RXD0/IO3_34") (pintype "bidirectional"))
      (node (ref "JP2") (pin "3") (pinfunction "3_3") (pintype "passive"))
      (node (ref "R5") (pin "2") (pinfunction "2_2") (pintype "passive"))
    )
    (net (code "82") (name "RXLED") (class "Default")
      (node (ref "IC1") (pin "13") (pinfunction "RXLED/IO1_13") (pintype "bidirectional"))
      (node (ref "RX") (pin "C") (pinfunction "C_C") (pintype "passive"))
    )
    (net (code "83") (name "SCK") (class "Default")
      (node (ref "ESP32") (pin "20") (pinfunction "SCK/IO6_20") (pintype "bidirectional"))
    )
    (net (code "84") (name "SD0") (class "Default")
      (node (ref "ESP32") (pin "21") (pinfunction "SDO/IO7_21") (pintype "bidirectional"))
    )
    (net (code "85") (name "SD1") (class "Default")
      (node (ref "ESP32") (pin "22") (pinfunction "SDI/IO8_22") (pintype "bidirectional"))
    )
    (net (code "86") (name "SD2") (class "Default")
      (node (ref "ESP32") (pin "17") (pinfunction "SHD/IO9_17") (pintype "bidirectional"))
    )
    (net (code "87") (name "SD3") (class "Default")
      (node (ref "ESP32") (pin "18") (pinfunction "SWP/IO10_18") (pintype "bidirectional"))
    )
    (net (code "88") (name "SET_V++") (class "Default")
      (node (ref "JP2") (pin "13") (pinfunction "13_13") (pintype "passive"))
      (node (ref "R43") (pin "2") (pinfunction "2_2") (pintype "passive"))
    )
    (net (code "89") (name "SVN") (class "Default")
      (node (ref "ESP32") (pin "5") (pinfunction "SVN/I039/A1C3_5") (pintype "bidirectional"))
      (node (ref "JP2") (pin "6") (pinfunction "6_6") (pintype "passive"))
    )
    (net (code "90") (name "SVP") (class "Default")
      (node (ref "ESP32") (pin "4") (pinfunction "SVP/I036/A1C0_4") (pintype "bidirectional"))
      (node (ref "JP2") (pin "5") (pinfunction "5_5") (pintype "passive"))
    )
    (net (code "91") (name "TXD0") (class "Default")
      (node (ref "ESP32") (pin "35") (pinfunction "TXD0/IO1_35") (pintype "bidirectional"))
      (node (ref "JP2") (pin "2") (pinfunction "2_2") (pintype "passive"))
      (node (ref "R46") (pin "2") (pinfunction "2_2") (pintype "passive"))
    )
    (net (code "92") (name "TXLED") (class "Default")
      (node (ref "IC1") (pin "14") (pinfunction "TXLED/IO0_14") (pintype "bidirectional"))
      (node (ref "TX") (pin "C") (pinfunction "C_C") (pintype "passive"))
    )
    (net (code "93") (name "V++") (class "Default")
      (node (ref "C21") (pin "1") (pinfunction "1_1") (pintype "passive"))
      (node (ref "C22") (pin "1") (pinfunction "1_1") (pintype "passive"))
      (node (ref "C26") (pin "+") (pinfunction "+_+") (pintype "passive"))
      (node (ref "D1") (pin "C") (pinfunction "C_C") (pintype "passive"))
      (node (ref "IC3") (pin "4") (pinfunction "EN_4") (pintype "bidirectional"))
      (node (ref "IC3") (pin "5") (pinfunction "VIN_5") (pintype "power_in"))
      (node (ref "JP2") (pin "12") (pinfunction "12_12") (pintype "passive"))
      (node (ref "L1") (pin "2") (pinfunction "2_2") (pintype "passive"))
      (node (ref "R39") (pin "1") (pinfunction "1_1") (pintype "passive"))
    )
    (net (code "94") (name "YELLOW") (class "Default")
      (node (ref "R22") (pin "1") (pinfunction "1_1") (pintype "passive"))
      (node (ref "U$1") (pin "2") (pinfunction "LED2/~{INTSEL}_2") (pintype "bidirectional"))
    )
    (net (code "95") (name "unconnected-(ESP32-NC-Pad32)") (class "Default")
      (node (ref "ESP32") (pin "32") (pinfunction "NC_32") (pintype "bidirectional"))
    )
    (net (code "96") (name "unconnected-(IC1-CLK{slash}~{RI}-Pad1)") (class "Default")
      (node (ref "IC1") (pin "1") (pinfunction "CLK/~{RI}_1") (pintype "bidirectional"))
    )
    (net (code "97") (name "unconnected-(IC1-RS485{slash}IO2-Pad12)") (class "Default")
      (node (ref "IC1") (pin "12") (pinfunction "RS485/IO2_12") (pintype "bidirectional"))
    )
    (net (code "98") (name "unconnected-(IC1-SUSPEND-Pad17)") (class "Default")
      (node (ref "IC1") (pin "17") (pinfunction "SUSPEND_17") (pintype "bidirectional"))
    )
    (net (code "99") (name "unconnected-(IC1-WAKEUP{slash}IO3-Pad11)") (class "Default")
      (node (ref "IC1") (pin "11") (pinfunction "WAKEUP/IO3_11") (pintype "bidirectional"))
    )
    (net (code "100") (name "unconnected-(IC1-~{CTS}-Pad18)") (class "Default")
      (node (ref "IC1") (pin "18") (pinfunction "~{CTS}_18") (pintype "bidirectional"))
    )
    (net (code "101") (name "unconnected-(IC1-~{DCD}-Pad24)") (class "Default")
      (node (ref "IC1") (pin "24") (pinfunction "~{DCD}_24") (pintype "bidirectional"))
    )
    (net (code "102") (name "unconnected-(IC1-~{DSR}-Pad22)") (class "Default")
      (node (ref "IC1") (pin "22") (pinfunction "~{DSR}_22") (pintype "bidirectional"))
    )
    (net (code "103") (name "unconnected-(IC1-~{SUSPEND}-Pad15)") (class "Default")
      (node (ref "IC1") (pin "15") (pinfunction "~{SUSPEND}_15") (pintype "bidirectional"))
    )
    (net (code "104") (name "unconnected-(U$1-REFCLKO{slash}~{INT}-Pad14)") (class "Default")
      (node (ref "U$1") (pin "14") (pinfunction "REFCLKO/~{INT}_14") (pintype "bidirectional"))
    )
    (net (code "105") (name "unconnected-(U$1-XTAL2-Pad4)") (class "Default")
      (node (ref "U$1") (pin "4") (pinfunction "XTAL2_4") (pintype "bidirectional"))
    )
    (net (code "106") (name "unconnected-(U1-PG-Pad6)") (class "Default")
      (node (ref "U1") (pin "6") (pinfunction "PG_6") (pintype "bidirectional"))
    )
    (net (code "107") (name "unconnected-(X5-Pad4)") (class "Default")
      (node (ref "X5") (pin "4") (pinfunction "4_4") (pintype "input"))
    )
  )
)
